# 464421_22-01_Switch_GPS_IO_Connectors.net
KiCad netlist of a schematic drawn in Altium Designer
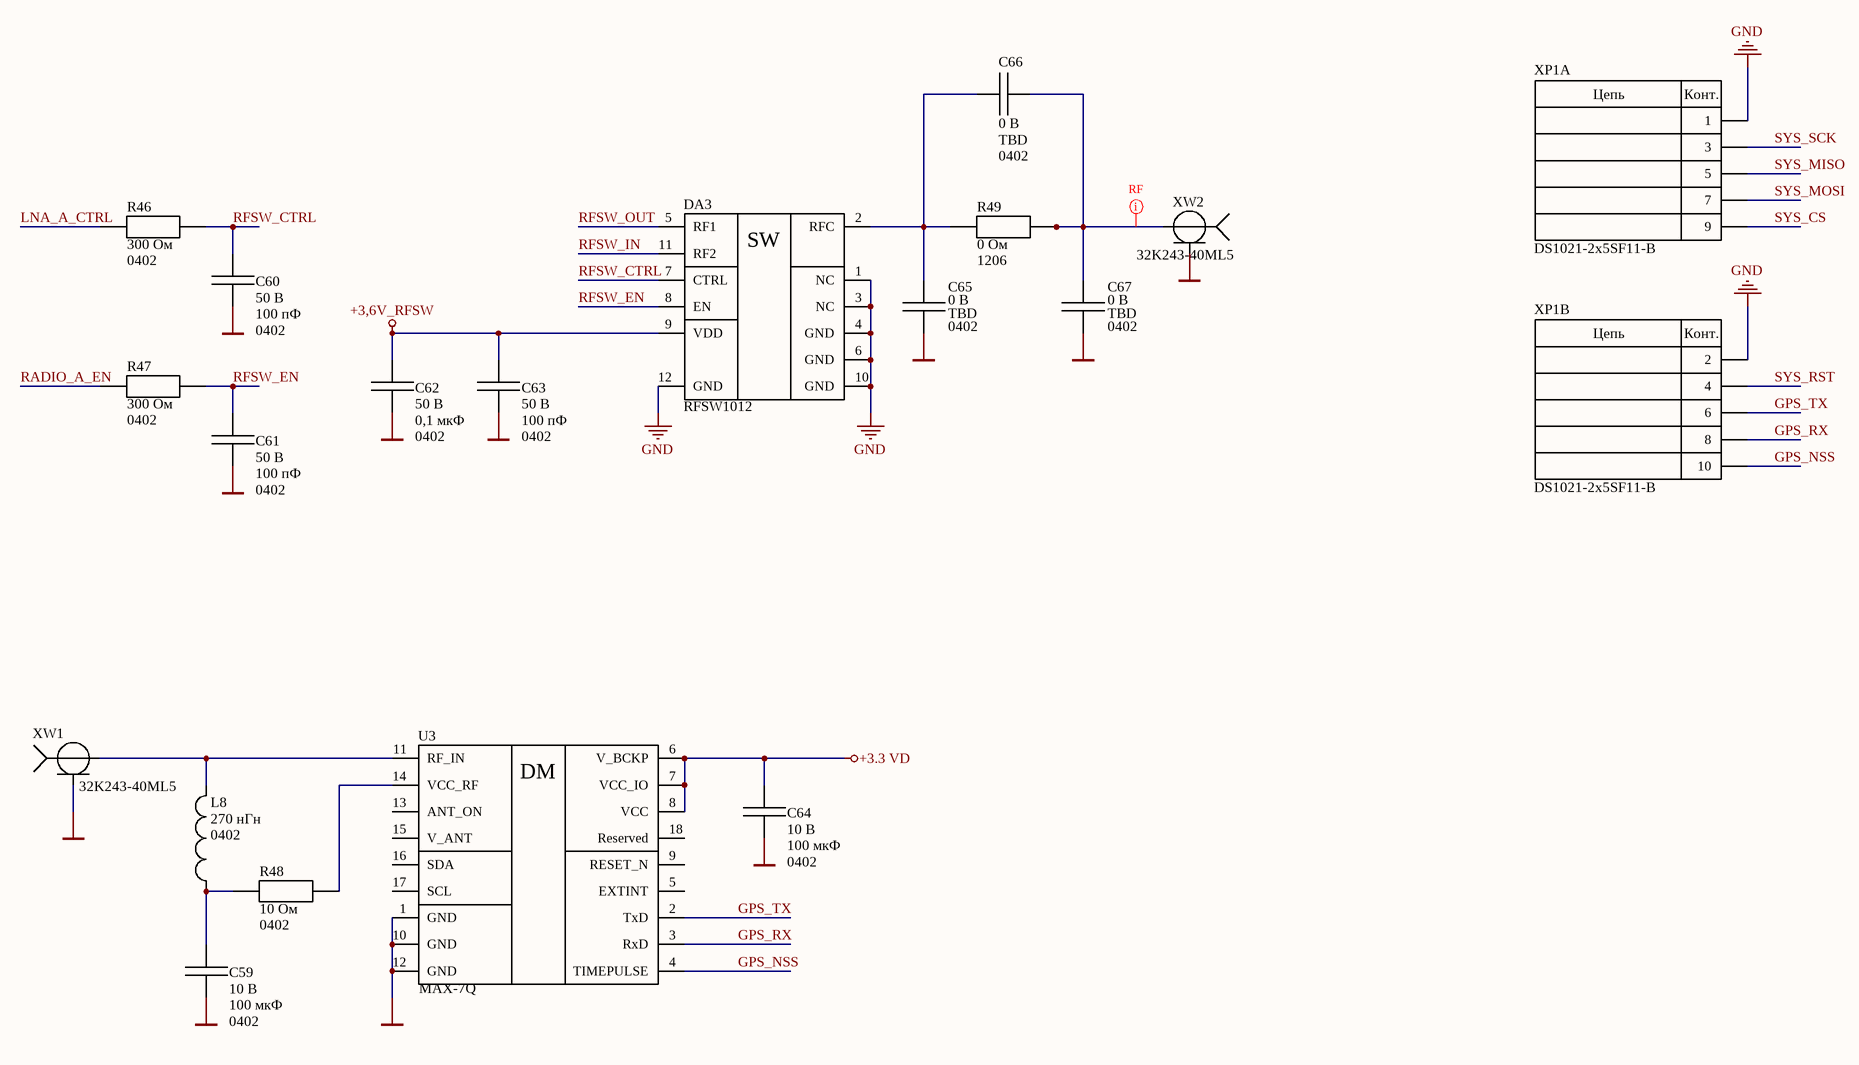
[diagram p0: МПСУ.464421.22-01 Switch,GPS, IO Connectors.SchDoc]

(export (version "E")
  (design (tool "Eeschema 10.0.6"))
  (components
    (comp (ref "C59")
      (value "100 мкФ")
      (footprint "Passive_V2_0:CAPC100X50X55L20N")
      (description "Capacitor 0402")
      (fields
        (field (name "PARTNUMBER") "C3216JB1A107M160AC")
        (field (name "MANUFACTURER") "TDK")
        (field (name "PEAK_CONDITION") "10 В")
        (field (name "PACKAGE") "0402")
        (field (name "DESIGNER") "Свидерский")
      )
      (libsource (lib "Passive_V2_0") (part "C 0402"))
    )
    (comp (ref "C60")
      (value "100 пФ")
      (footprint "Passive_V2_0:CAPC100X50X55L20N")
      (description "Capacitor 0402")
      (fields
        (field (name "PARTNUMBER") "GRM1555C1H101JZ01D")
        (field (name "MANUFACTURER") "Murata")
        (field (name "PEAK_CONDITION") "50 В")
        (field (name "PACKAGE") "0402")
        (field (name "DESIGNER") "Свидерский")
      )
      (libsource (lib "Passive_V2_0") (part "C 0402"))
    )
    (comp (ref "C61")
      (value "100 пФ")
      (footprint "Passive_V2_0:CAPC100X50X55L20N")
      (description "Capacitor 0402")
      (fields
        (field (name "PARTNUMBER") "GRM1555C1H101JZ01D")
        (field (name "MANUFACTURER") "Murata")
        (field (name "PEAK_CONDITION") "50 В")
        (field (name "PACKAGE") "0402")
        (field (name "DESIGNER") "Свидерский")
      )
      (libsource (lib "Passive_V2_0") (part "C 0402"))
    )
    (comp (ref "C62")
      (value "0,1 мкФ")
      (footprint "Passive_V2_0:CAPC100X50X55L20N")
      (description "Capacitor 0402")
      (fields
        (field (name "PARTNUMBER") "GRM155R71H104KE14J")
        (field (name "MANUFACTURER") "Murata")
        (field (name "PEAK_CONDITION") "50 В")
        (field (name "PACKAGE") "0402")
        (field (name "DESIGNER") "Свидерский")
      )
      (libsource (lib "Passive_V2_0") (part "C 0402"))
    )
    (comp (ref "C63")
      (value "100 пФ")
      (footprint "Passive_V2_0:CAPC100X50X55L20N")
      (description "Capacitor 0402")
      (fields
        (field (name "PARTNUMBER") "GRM1555C1H101JZ01D")
        (field (name "MANUFACTURER") "Murata")
        (field (name "PEAK_CONDITION") "50 В")
        (field (name "PACKAGE") "0402")
        (field (name "DESIGNER") "Свидерский")
      )
      (libsource (lib "Passive_V2_0") (part "C 0402"))
    )
    (comp (ref "C64")
      (value "100 мкФ")
      (footprint "Passive_V2_0:CAPC100X50X55L20N")
      (description "Capacitor 0402")
      (fields
        (field (name "PARTNUMBER") "C3216JB1A107M160AC")
        (field (name "MANUFACTURER") "TDK")
        (field (name "PEAK_CONDITION") "10 В")
        (field (name "PACKAGE") "0402")
        (field (name "DESIGNER") "Свидерский")
      )
      (libsource (lib "Passive_V2_0") (part "C 0402"))
    )
    (comp (ref "C65")
      (value "TBD")
      (footprint "Passive_V2_0:CAPC100X50X55L20N")
      (description "Capacitor 0402")
      (fields
        (field (name "TOLERANCE") "0 %")
        (field (name "PEAK_CONDITION") "0 В")
        (field (name "PACKAGE") "0402")
        (field (name "Comment") "TBD 0402")
        (field (name "DESIGNER") "Свидерский")
      )
      (libsource (lib "Passive_V2_0") (part "C 0402"))
    )
    (comp (ref "C66")
      (value "TBD")
      (footprint "Passive_V2_0:CAPC100X50X55L20N")
      (description "Capacitor 0402")
      (fields
        (field (name "TOLERANCE") "0 %")
        (field (name "PEAK_CONDITION") "0 В")
        (field (name "PACKAGE") "0402")
        (field (name "Comment") "TBD 0402")
        (field (name "DESIGNER") "Свидерский")
      )
      (libsource (lib "Passive_V2_0") (part "C 0402"))
    )
    (comp (ref "C67")
      (value "TBD")
      (footprint "Passive_V2_0:CAPC100X50X55L20N")
      (description "Capacitor 0402")
      (fields
        (field (name "TOLERANCE") "0 %")
        (field (name "PEAK_CONDITION") "0 В")
        (field (name "PACKAGE") "0402")
        (field (name "Comment") "TBD 0402")
        (field (name "DESIGNER") "Свидерский")
      )
      (libsource (lib "Passive_V2_0") (part "C 0402"))
    )
    (comp (ref "DA3")
      (value "RFSW1012")
      (footprint "IC_V2_0:PQFN50P200X200X60_HS-13N")
      (description "Broadband SPDT Switch 0.005-6 GHz")
      (fields
        (field (name "MANUFACTURER") "Qorvo")
        (field (name "PARTNUMBER") "RFSW1012")
        (field (name "DESIGNER") "Лазба")
      )
      (libsource (lib "IC_V2_0") (part "RFSW1012"))
    )
    (comp (ref "L8")
      (value "270 нГн")
      (footprint "Passive_V2_0:INDC100X50X60L10N")
      (description "Inductor 0402")
      (fields
        (field (name "PARTNUMBER") "LQG15HSR27J02D")
        (field (name "TOLERANCE") "5 %")
        (field (name "PACKAGE") "0402")
        (field (name "DESIGNER") "Свидерский")
      )
      (libsource (lib "Passive_V2_0") (part "L 0402"))
    )
    (comp (ref "R46")
      (value "300 Ом")
      (footprint "Passive_V2_0:RESC100X50X40L25N")
      (description "Resistor 0402")
      (fields
        (field (name "PARTNUMBER") "RI0402L301JT")
        (field (name "TOLERANCE") "5 %")
        (field (name "PACKAGE") "0402")
        (field (name "DESIGNER") "Свидерский")
      )
      (libsource (lib "Passive_V2_0") (part "R 0402"))
    )
    (comp (ref "R47")
      (value "300 Ом")
      (footprint "Passive_V2_0:RESC100X50X40L25N")
      (description "Resistor 0402")
      (fields
        (field (name "PARTNUMBER") "RI0402L301JT")
        (field (name "TOLERANCE") "5 %")
        (field (name "PACKAGE") "0402")
        (field (name "DESIGNER") "Свидерский")
      )
      (libsource (lib "Passive_V2_0") (part "R 0402"))
    )
    (comp (ref "R48")
      (value "10 Ом")
      (footprint "Passive_V2_0:RESC100X50X40L25N")
      (description "Resistor 0402")
      (fields
        (field (name "PARTNUMBER") "RI0402L100JT")
        (field (name "TOLERANCE") "5 %")
        (field (name "PACKAGE") "0402")
        (field (name "DESIGNER") "Свидерский")
      )
      (libsource (lib "Passive_V2_0") (part "R 0402"))
    )
    (comp (ref "R49")
      (value "0 Ом")
      (footprint "Passive_V2_0:RESC310X160X55L50N")
      (description "Resistor 1206")
      (fields
        (field (name "PARTNUMBER") "RI1206L000JT")
        (field (name "TOLERANCE") "5 %")
        (field (name "PACKAGE") "1206")
        (field (name "DESIGNER") "Свидерский")
      )
      (libsource (lib "Passive_V2_0") (part "R 1206"))
    )
    (comp (ref "U3")
      (value "MAX-7Q")
      (footprint "IC_V2_0:MAX-7-Q0")
      (description "GPS/GNSS Module")
      (fields
        (field (name "MANUFACTURER") "u-blox")
        (field (name "PARTNUMBER") "MAX-7Q")
        (field (name "DESIGNER") "Лазба")
      )
      (libsource (lib "IC_V2_0") (part "MAX-7-*"))
    )
    (comp (ref "XP1")
      (value "DS1021-2x5SF11-B")
      (footprint "Connectors_V2_0:HDRV10W64P254_5X2_1270X508H854")
      (description "Вилка 2,54мм")
      (fields
        (field (name "MANUFACTURER") "Connfly Electronic")
        (field (name "PARTNUMBER") "DS1021-2x5SF11-B")
        (field (name "DESIGNER") "Свидерский")
      )
      (libsource (lib "Connectors_V2_0") (part "DS1021-2x5SF11-B"))
    )
    (comp (ref "XW1")
      (value "32K243-40ML5")
      (footprint "Connectors_V2_0:32K243-40ML5")
      (description "RF connector, Right Angle Jack PCB SMA Female End Launch Connector")
      (fields
        (field (name "MANUFACTURER") "Rosenberger")
        (field (name "PARTNUMBER") "32K243-40ML5")
        (field (name "DESIGNER") "Шеремет")
      )
      (libsource (lib "Connectors_V2_0") (part "32K243-40ML5"))
    )
    (comp (ref "XW2")
      (value "32K243-40ML5")
      (footprint "Connectors_V2_0:32K243-40ML5")
      (description "RF connector, Right Angle Jack PCB SMA Female End Launch Connector")
      (fields
        (field (name "MANUFACTURER") "Rosenberger")
        (field (name "PARTNUMBER") "32K243-40ML5")
        (field (name "DESIGNER") "Шеремет")
      )
      (libsource (lib "Connectors_V2_0") (part "32K243-40ML5"))
    )
  )
  (nets
    (net (code "1") (name "+3,6V_RFSW") (class "Default")
      (node (ref "C62") (pin "2") (pinfunction "2_2") (pintype "passive"))
      (node (ref "C63") (pin "2") (pinfunction "2_2") (pintype "passive"))
      (node (ref "DA3") (pin "9") (pinfunction "VDD_9") (pintype "passive"))
    )
    (net (code "2") (name "+3.3 VD") (class "Default")
      (node (ref "C64") (pin "1") (pinfunction "1_1") (pintype "passive"))
      (node (ref "U3") (pin "6") (pinfunction "V_BCKP_6") (pintype "passive"))
      (node (ref "U3") (pin "7") (pinfunction "VCC_IO_7") (pintype "passive"))
      (node (ref "U3") (pin "8") (pinfunction "VCC_8") (pintype "passive"))
    )
    (net (code "4") (name "/GPS_NSS") (class "Default")
      (node (ref "U3") (pin "4") (pinfunction "TIMEPULSE_4") (pintype "passive"))
      (node (ref "XP1") (pin "10") (pinfunction "10_10") (pintype "passive"))
    )
    (net (code "5") (name "/GPS_RX") (class "Default")
      (node (ref "U3") (pin "3") (pinfunction "RxD_3") (pintype "passive"))
      (node (ref "XP1") (pin "8") (pinfunction "8_8") (pintype "passive"))
    )
    (net (code "6") (name "/GPS_TX") (class "Default")
      (node (ref "U3") (pin "2") (pinfunction "TxD_2") (pintype "passive"))
      (node (ref "XP1") (pin "6") (pinfunction "6_6") (pintype "passive"))
    )
    (net (code "7") (name "/LNA_A_CTRL") (class "Default")
      (node (ref "R46") (pin "1") (pinfunction "1_1") (pintype "passive"))
    )
    (net (code "8") (name "/RADIO_A_EN") (class "Default")
      (node (ref "R47") (pin "1") (pinfunction "1_1") (pintype "passive"))
    )
    (net (code "9") (name "/RFSW_CTRL") (class "Default")
      (node (ref "C60") (pin "2") (pinfunction "2_2") (pintype "passive"))
      (node (ref "DA3") (pin "7") (pinfunction "CTRL_7") (pintype "passive"))
      (node (ref "R46") (pin "2") (pinfunction "2_2") (pintype "passive"))
    )
    (net (code "10") (name "/RFSW_EN") (class "Default")
      (node (ref "C61") (pin "2") (pinfunction "2_2") (pintype "passive"))
      (node (ref "DA3") (pin "8") (pinfunction "EN_8") (pintype "passive"))
      (node (ref "R47") (pin "2") (pinfunction "2_2") (pintype "passive"))
    )
    (net (code "11") (name "/RFSW_IN") (class "Default")
      (node (ref "DA3") (pin "11") (pinfunction "RF2_11") (pintype "passive"))
    )
    (net (code "12") (name "/RFSW_OUT") (class "Default")
      (node (ref "DA3") (pin "5") (pinfunction "RF1_5") (pintype "passive"))
    )
    (net (code "13") (name "/SYS_CS") (class "Default")
      (node (ref "XP1") (pin "9") (pinfunction "9_9") (pintype "passive"))
    )
    (net (code "14") (name "/SYS_MISO") (class "Default")
      (node (ref "XP1") (pin "5") (pinfunction "5_5") (pintype "passive"))
    )
    (net (code "15") (name "/SYS_MOSI") (class "Default")
      (node (ref "XP1") (pin "7") (pinfunction "7_7") (pintype "passive"))
    )
    (net (code "16") (name "/SYS_RST") (class "Default")
      (node (ref "XP1") (pin "4") (pinfunction "4_4") (pintype "passive"))
    )
    (net (code "17") (name "/SYS_SCK") (class "Default")
      (node (ref "XP1") (pin "3") (pinfunction "3_3") (pintype "passive"))
    )
    (net (code "18") (name "GND") (class "Default")
      (node (ref "C59") (pin "2") (pinfunction "2_2") (pintype "passive"))
      (node (ref "C60") (pin "1") (pinfunction "1_1") (pintype "passive"))
      (node (ref "C61") (pin "1") (pinfunction "1_1") (pintype "passive"))
      (node (ref "C62") (pin "1") (pinfunction "1_1") (pintype "passive"))
      (node (ref "C63") (pin "1") (pinfunction "1_1") (pintype "passive"))
      (node (ref "C64") (pin "2") (pinfunction "2_2") (pintype "passive"))
      (node (ref "C65") (pin "1") (pinfunction "1_1") (pintype "passive"))
      (node (ref "C67") (pin "1") (pinfunction "1_1") (pintype "passive"))
      (node (ref "DA3") (pin "1") (pinfunction "NC_1") (pintype "passive"))
      (node (ref "DA3") (pin "10") (pinfunction "GND_10") (pintype "passive"))
      (node (ref "DA3") (pin "12") (pinfunction "GND_12") (pintype "passive"))
      (node (ref "DA3") (pin "3") (pinfunction "NC_3") (pintype "passive"))
      (node (ref "DA3") (pin "4") (pinfunction "GND_4") (pintype "passive"))
      (node (ref "DA3") (pin "6") (pinfunction "GND_6") (pintype "passive"))
      (node (ref "U3") (pin "1") (pinfunction "GND_1") (pintype "passive"))
      (node (ref "U3") (pin "10") (pinfunction "GND_10") (pintype "passive"))
      (node (ref "U3") (pin "12") (pinfunction "GND_12") (pintype "passive"))
      (node (ref "XP1") (pin "1") (pinfunction "1_1") (pintype "passive"))
      (node (ref "XP1") (pin "2") (pinfunction "2_2") (pintype "passive"))
      (node (ref "XW1") (pin "2") (pinfunction "GND_2") (pintype "passive"))
      (node (ref "XW2") (pin "2") (pinfunction "GND_2") (pintype "passive"))
    )
    (net (code "19") (name "Net-(C59-Pad1)") (class "Default")
      (node (ref "C59") (pin "1") (pinfunction "1_1") (pintype "passive"))
      (node (ref "L8") (pin "1") (pinfunction "1_1") (pintype "passive"))
      (node (ref "R48") (pin "1") (pinfunction "1_1") (pintype "passive"))
    )
    (net (code "20") (name "Net-(DA3-RFC)") (class "Default")
      (node (ref "C65") (pin "2") (pinfunction "2_2") (pintype "passive"))
      (node (ref "C66") (pin "2") (pinfunction "2_2") (pintype "passive"))
      (node (ref "DA3") (pin "2") (pinfunction "RFC_2") (pintype "passive"))
      (node (ref "R49") (pin "1") (pinfunction "1_1") (pintype "passive"))
    )
    (net (code "21") (name "Net-(U3-RF_IN)") (class "Default")
      (node (ref "L8") (pin "2") (pinfunction "2_2") (pintype "passive"))
      (node (ref "U3") (pin "11") (pinfunction "RF_IN_11") (pintype "passive"))
      (node (ref "XW1") (pin "1") (pinfunction "RF_1") (pintype "passive"))
    )
    (net (code "22") (name "Net-(U3-VCC_RF)") (class "Default")
      (node (ref "R48") (pin "2") (pinfunction "2_2") (pintype "passive"))
      (node (ref "U3") (pin "14") (pinfunction "VCC_RF_14") (pintype "passive"))
    )
    (net (code "23") (name "Net-(XW2-RF)") (class "Default")
      (node (ref "C66") (pin "1") (pinfunction "1_1") (pintype "passive"))
      (node (ref "C67") (pin "2") (pinfunction "2_2") (pintype "passive"))
      (node (ref "R49") (pin "2") (pinfunction "2_2") (pintype "passive"))
      (node (ref "XW2") (pin "1") (pinfunction "RF_1") (pintype "passive"))
    )
    (net (code "24") (name "unconnected-(U3-ANT_ON-Pad13)") (class "Default")
      (node (ref "U3") (pin "13") (pinfunction "ANT_ON_13") (pintype "passive"))
    )
    (net (code "25") (name "unconnected-(U3-EXTINT-Pad5)") (class "Default")
      (node (ref "U3") (pin "5") (pinfunction "EXTINT_5") (pintype "passive"))
    )
    (net (code "26") (name "unconnected-(U3-RESET_N-Pad9)") (class "Default")
      (node (ref "U3") (pin "9") (pinfunction "RESET_N_9") (pintype "passive"))
    )
    (net (code "27") (name "unconnected-(U3-Reserved-Pad18)") (class "Default")
      (node (ref "U3") (pin "18") (pinfunction "Reserved_18") (pintype "passive"))
    )
    (net (code "28") (name "unconnected-(U3-SCL-Pad17)") (class "Default")
      (node (ref "U3") (pin "17") (pinfunction "SCL_17") (pintype "passive"))
    )
    (net (code "29") (name "unconnected-(U3-SDA-Pad16)") (class "Default")
      (node (ref "U3") (pin "16") (pinfunction "SDA_16") (pintype "passive"))
    )
    (net (code "30") (name "unconnected-(U3-V_ANT-Pad15)") (class "Default")
      (node (ref "U3") (pin "15") (pinfunction "V_ANT_15") (pintype "passive"))
    )
  )
)
